# horus_psu.net
KiCad netlist of a schematic drawn in Altium Designer
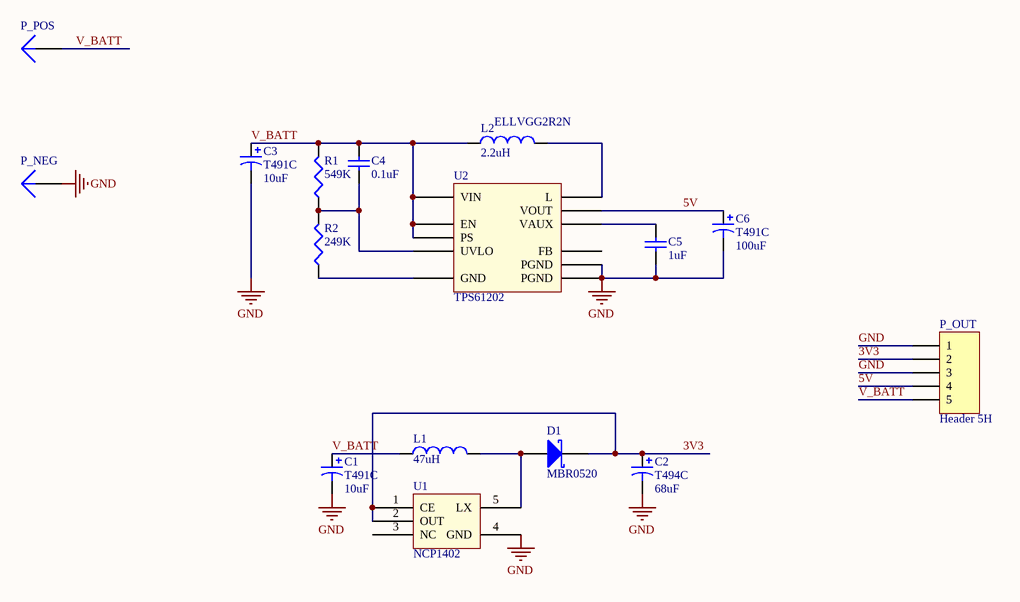
[diagram p0: horus_psu.SchDoc]

(export (version "E")
  (design (tool "Eeschema 10.0.6"))
  (components
    (comp (ref "C1")
      (value "T491C")
      (footprint "C")
      (description "Solid Tantalum Chip Capacitor, Standard T491 Series - Industrial Grade")
      (fields (field (name "ALTIUM_VALUE") "10uF") (field (name "PUBLISHER") "Altium Limited"))
      (libsource (lib "KEMET Chip Capacitor") (part "T491C"))
    )
    (comp (ref "C2")
      (value "T494C")
      (footprint "C")
      (description "Solid Tantalum Chip Capacitor, Standard T494 Series - Low ESR, Industrial Grade")
      (fields (field (name "ALTIUM_VALUE") "68uF") (field (name "PUBLISHER") "Altium Limited"))
      (libsource (lib "KEMET Chip Capacitor") (part "T494C"))
    )
    (comp (ref "C3")
      (value "T491C")
      (footprint "C")
      (description "Solid Tantalum Chip Capacitor, Standard T491 Series - Industrial Grade")
      (fields (field (name "ALTIUM_VALUE") "10uF") (field (name "PUBLISHER") "Altium Limited"))
      (libsource (lib "KEMET Chip Capacitor") (part "T491C"))
    )
    (comp (ref "C4")
      (value "0.1uF")
      (footprint "1608[0603]")
      (description "Capacitor (Semiconductor SIM Model)")
      (fields (field (name "Comment") "Cap Semi") (field (name "PUBLISHER") "Altium Limited"))
      (libsource (lib "Miscellaneous Devices") (part "Cap Semi"))
    )
    (comp (ref "C5")
      (value "1uF")
      (footprint "1608[0603]")
      (description "Capacitor (Semiconductor SIM Model)")
      (fields (field (name "Comment") "Cap Semi") (field (name "PUBLISHER") "Altium Limited"))
      (libsource (lib "Miscellaneous Devices") (part "Cap Semi"))
    )
    (comp (ref "C6")
      (value "T491C")
      (footprint "C")
      (description "Solid Tantalum Chip Capacitor, Standard T491 Series - Industrial Grade")
      (fields (field (name "ALTIUM_VALUE") "100uF") (field (name "PUBLISHER") "Altium Limited"))
      (libsource (lib "KEMET Chip Capacitor") (part "T491C"))
    )
    (comp (ref "D1")
      (value "MBR0520")
      (footprint "SOD-123")
      (description "Silicon AF Schottky Diode for High-Speed Switching")
      (fields (field (name "PUBLISHER") "Altium Limited"))
      (libsource (lib "Miscellaneous Devices") (part "Diode BAS70"))
    )
    (comp (ref "L1")
      (value "47uH")
      (footprint "POWER-CHOKE_47uH")
      (description "Inductor")
      (fields (field (name "PUBLISHER") "Altium Limited"))
      (libsource (lib "Miscellaneous Devices") (part "Inductor"))
    )
    (comp (ref "L2")
      (value "ELLVGG2R2N")
      (footprint "ELLVGG")
      (description "Inductor")
      (fields (field (name "ALTIUM_VALUE") "2.2uH") (field (name "PUBLISHER") "Altium Limited"))
      (libsource (lib "Miscellaneous Devices") (part "Inductor"))
    )
    (comp (ref "P_NEG")
      (value "Plug")
      (footprint "PIN1")
      (fields (field (name "PUBLISHER") "Altium Limited"))
      (libsource (lib "Miscellaneous Connectors") (part "Plug"))
    )
    (comp (ref "P_OUT")
      (value "Header 5H")
      (footprint "HDR1X5H")
      (description "Header, 5-Pin, Right Angle")
      (fields (field (name "PUBLISHER") "Altium Limited"))
      (libsource (lib "Miscellaneous Connectors") (part "Header 5H"))
    )
    (comp (ref "P_POS")
      (value "Plug")
      (footprint "PIN1")
      (fields (field (name "PUBLISHER") "Altium Limited"))
      (libsource (lib "Miscellaneous Connectors") (part "Plug"))
    )
    (comp (ref "R1")
      (value "549K")
      (footprint "J1-0603")
      (description "Resistor")
      (fields (field (name "Comment") "Res3") (field (name "PUBLISHER") "Altium Limited"))
      (libsource (lib "Miscellaneous Devices") (part "Res3"))
    )
    (comp (ref "R2")
      (value "249K")
      (footprint "J1-0603")
      (description "Resistor")
      (fields (field (name "Comment") "Res3") (field (name "PUBLISHER") "Altium Limited"))
      (libsource (lib "Miscellaneous Devices") (part "Res3"))
    )
    (comp (ref "U1")
      (value "NCP1402")
      (footprint "SOT95P280X100-5N")
      (libsource (lib "horus_psu") (part "NCP1402"))
    )
    (comp (ref "U2")
      (value "TPS61202")
      (footprint "TPS61200")
      (libsource (lib "horus_psu") (part "TPS61200"))
    )
  )
  (nets
    (net (code "1") (name "/3V3") (class "Default")
      (node (ref "C2") (pin "1") (pinfunction "1_1") (pintype "passive"))
      (node (ref "D1") (pin "1") (pinfunction "K_1") (pintype "passive"))
      (node (ref "P_OUT") (pin "2") (pinfunction "2_2") (pintype "passive"))
      (node (ref "U1") (pin "1") (pinfunction "CE_1") (pintype "passive"))
      (node (ref "U1") (pin "2") (pinfunction "OUT_2") (pintype "passive"))
    )
    (net (code "2") (name "/5V") (class "Default")
      (node (ref "C6") (pin "1") (pinfunction "1_1") (pintype "passive"))
      (node (ref "P_OUT") (pin "4") (pinfunction "4_4") (pintype "passive"))
      (node (ref "U2") (pin "2") (pinfunction "VOUT_2") (pintype "passive"))
    )
    (net (code "3") (name "/V_BATT") (class "Default")
      (node (ref "C1") (pin "1") (pinfunction "1_1") (pintype "passive"))
      (node (ref "C3") (pin "1") (pinfunction "1_1") (pintype "passive"))
      (node (ref "C4") (pin "2") (pinfunction "2_2") (pintype "passive"))
      (node (ref "L1") (pin "1") (pinfunction "1_1") (pintype "passive"))
      (node (ref "L2") (pin "1") (pinfunction "1_1") (pintype "passive"))
      (node (ref "P_OUT") (pin "5") (pinfunction "5_5") (pintype "passive"))
      (node (ref "P_POS") (pin "1") (pinfunction "1_1") (pintype "passive"))
      (node (ref "R1") (pin "2") (pinfunction "2_2") (pintype "passive"))
      (node (ref "U2") (pin "5") (pinfunction "VIN_5") (pintype "passive"))
      (node (ref "U2") (pin "6") (pinfunction "EN_6") (pintype "passive"))
      (node (ref "U2") (pin "8") (pinfunction "PS_8") (pintype "passive"))
    )
    (net (code "4") (name "GND") (class "Default")
      (node (ref "C1") (pin "2") (pinfunction "2_2") (pintype "passive"))
      (node (ref "C2") (pin "2") (pinfunction "2_2") (pintype "passive"))
      (node (ref "C3") (pin "2") (pinfunction "2_2") (pintype "passive"))
      (node (ref "C5") (pin "1") (pinfunction "1_1") (pintype "passive"))
      (node (ref "C6") (pin "2") (pinfunction "2_2") (pintype "passive"))
      (node (ref "P_NEG") (pin "1") (pinfunction "1_1") (pintype "passive"))
      (node (ref "P_OUT") (pin "1") (pinfunction "1_1") (pintype "passive"))
      (node (ref "P_OUT") (pin "3") (pinfunction "3_3") (pintype "passive"))
      (node (ref "U1") (pin "4") (pinfunction "GND_4") (pintype "passive"))
      (node (ref "U2") (pin "0") (pinfunction "PGND_0") (pintype "passive"))
      (node (ref "U2") (pin "4") (pinfunction "PGND_4") (pintype "passive"))
    )
    (net (code "5") (name "Net-(D1-A)") (class "Default")
      (node (ref "D1") (pin "2") (pinfunction "A_2") (pintype "passive"))
      (node (ref "L1") (pin "2") (pinfunction "2_2") (pintype "passive"))
      (node (ref "U1") (pin "5") (pinfunction "LX_5") (pintype "passive"))
    )
    (net (code "6") (name "Net-(U2-GND)") (class "Default")
      (node (ref "R2") (pin "1") (pinfunction "1_1") (pintype "passive"))
      (node (ref "U2") (pin "9") (pinfunction "GND_9") (pintype "passive"))
    )
    (net (code "7") (name "Net-(U2-L)") (class "Default")
      (node (ref "L2") (pin "2") (pinfunction "2_2") (pintype "passive"))
      (node (ref "U2") (pin "3") (pinfunction "L_3") (pintype "passive"))
    )
    (net (code "8") (name "Net-(U2-UVLO)") (class "Default")
      (node (ref "C4") (pin "1") (pinfunction "1_1") (pintype "passive"))
      (node (ref "R1") (pin "1") (pinfunction "1_1") (pintype "passive"))
      (node (ref "R2") (pin "2") (pinfunction "2_2") (pintype "passive"))
      (node (ref "U2") (pin "7") (pinfunction "UVLO_7") (pintype "passive"))
    )
    (net (code "9") (name "Net-(U2-VAUX)") (class "Default")
      (node (ref "C5") (pin "2") (pinfunction "2_2") (pintype "passive"))
      (node (ref "U2") (pin "1") (pinfunction "VAUX_1") (pintype "passive"))
    )
    (net (code "10") (name "unconnected-(U1-NC-Pad3)") (class "Default")
      (node (ref "U1") (pin "3") (pinfunction "NC_3") (pintype "passive"))
    )
    (net (code "11") (name "unconnected-(U2-FB-Pad10)") (class "Default")
      (node (ref "U2") (pin "10") (pinfunction "FB_10") (pintype "passive"))
    )
  )
)
